# POWER.net
KiCad netlist of a schematic drawn in Altium Designer
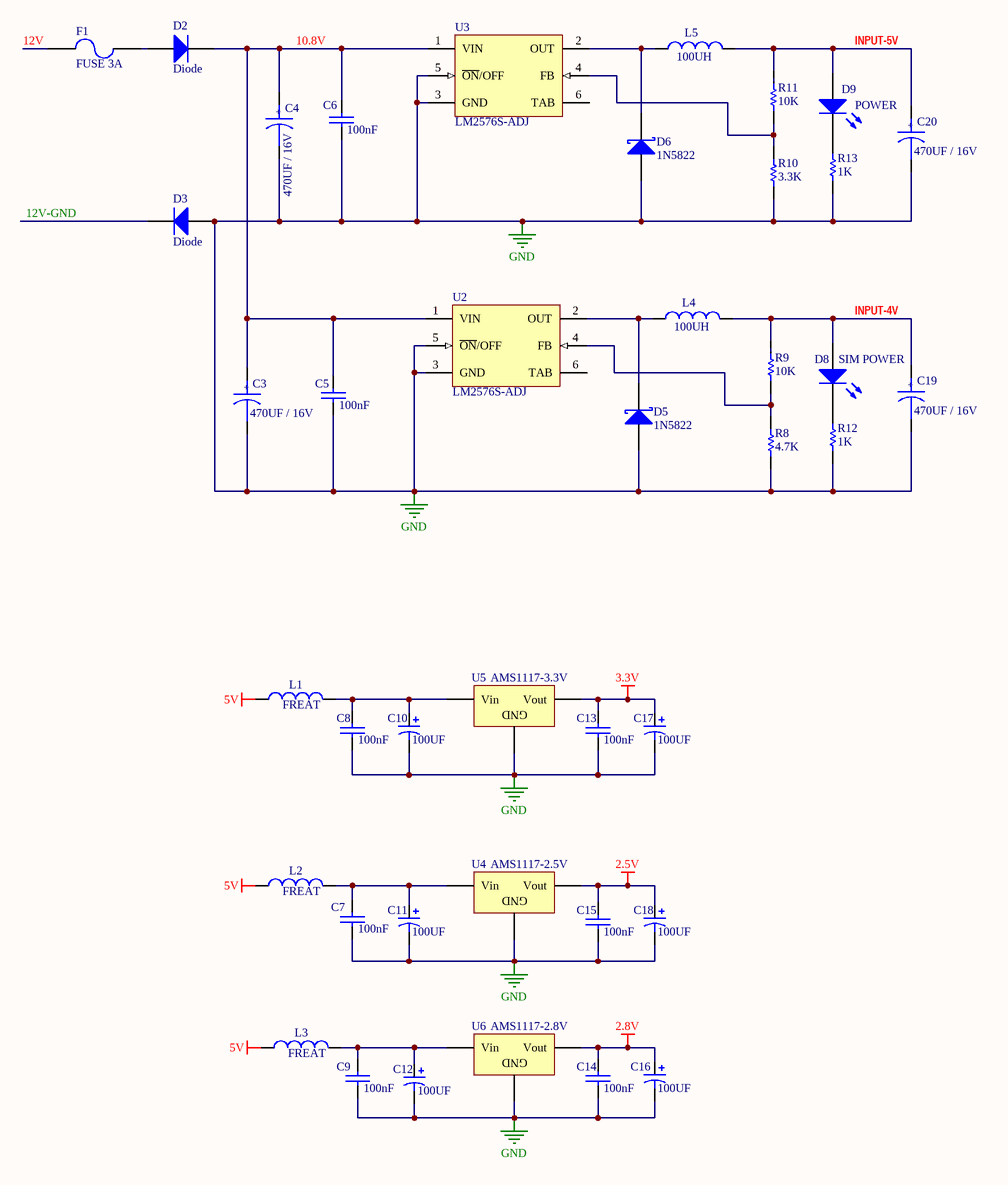
[diagram p0: POWER.SchDoc]

(export (version "E")
  (design (tool "Eeschema 10.0.6"))
  (components
    (comp (ref "C3")
      (value "470UF / 16V")
      (footprint "470UF-SMD")
      (description "Capacitor")
      (libsource (lib "*") (part "CAPACITOR POL"))
    )
    (comp (ref "C4")
      (value "470UF / 16V")
      (footprint "470UF-SMD")
      (description "Capacitor")
      (libsource (lib "*") (part "CAPACITOR POL"))
    )
    (comp (ref "C5") (value "100nF") (footprint "0805C") (libsource (lib "*") (part "CAP")))
    (comp (ref "C6") (value "100nF") (footprint "0805C") (libsource (lib "*") (part "CAP")))
    (comp (ref "C7") (value "100nF") (footprint "0805C") (libsource (lib "*") (part "CAP")))
    (comp (ref "C8") (value "100nF") (footprint "0805C") (libsource (lib "*") (part "CAP")))
    (comp (ref "C9") (value "100nF") (footprint "0805C") (libsource (lib "*") (part "CAP")))
    (comp (ref "C10")
      (value "100UF")
      (footprint "100UF-SMD")
      (description "Polarized Capacitor (Radial)")
      (fields (field (name "Comment") "100uF / 16V SMD") (field (name "PUBLISHER") "Altium Limited"))
      (libsource (lib "Miscellaneous Devices") (part "Cap Pol1"))
    )
    (comp (ref "C11")
      (value "100UF")
      (footprint "100uf-smd")
      (description "Polarized Capacitor (Radial)")
      (fields (field (name "Comment") "100uF / 16V SMD") (field (name "PUBLISHER") "Altium Limited"))
      (libsource (lib "Miscellaneous Devices") (part "Cap Pol1"))
    )
    (comp (ref "C12")
      (value "100UF")
      (footprint "100uf-smd")
      (description "Polarized Capacitor (Radial)")
      (fields (field (name "Comment") "100uF / 16V SMD") (field (name "PUBLISHER") "Altium Limited"))
      (libsource (lib "Miscellaneous Devices") (part "Cap Pol1"))
    )
    (comp (ref "C13") (value "100nF") (footprint "0805C") (libsource (lib "*") (part "CAP")))
    (comp (ref "C14") (value "100nF") (footprint "0805C") (libsource (lib "*") (part "CAP")))
    (comp (ref "C15") (value "100nF") (footprint "0805C") (libsource (lib "*") (part "CAP")))
    (comp (ref "C16")
      (value "100UF")
      (footprint "100uf-smd")
      (description "Polarized Capacitor (Radial)")
      (fields (field (name "Comment") "100uF / 16V SMD") (field (name "PUBLISHER") "Altium Limited"))
      (libsource (lib "Miscellaneous Devices") (part "Cap Pol1"))
    )
    (comp (ref "C17")
      (value "100UF")
      (footprint "100uf-smd")
      (description "Polarized Capacitor (Radial)")
      (fields (field (name "Comment") "100uF / 16V SMD") (field (name "PUBLISHER") "Altium Limited"))
      (libsource (lib "Miscellaneous Devices") (part "Cap Pol1"))
    )
    (comp (ref "C18")
      (value "100UF")
      (footprint "100uf-smd")
      (description "Polarized Capacitor (Radial)")
      (fields (field (name "Comment") "100uF / 16V SMD") (field (name "PUBLISHER") "Altium Limited"))
      (libsource (lib "Miscellaneous Devices") (part "Cap Pol1"))
    )
    (comp (ref "C19")
      (value "470UF / 16V")
      (footprint "470UF-SMD")
      (description "Capacitor")
      (libsource (lib "*") (part "CAPACITOR POL"))
    )
    (comp (ref "C20")
      (value "470UF / 16V")
      (footprint "470UF-SMD")
      (description "Capacitor")
      (libsource (lib "*") (part "CAPACITOR POL"))
    )
    (comp (ref "D2")
      (value "Diode")
      (footprint "Diode")
      (description "Default Diode")
      (fields (field (name "PUBLISHER") "Altium Limited"))
      (libsource (lib "Miscellaneous Devices") (part "Diode"))
    )
    (comp (ref "D3")
      (value "Diode")
      (footprint "Diode")
      (description "Default Diode")
      (fields (field (name "PUBLISHER") "Altium Limited"))
      (libsource (lib "Miscellaneous Devices") (part "Diode"))
    )
    (comp (ref "D5")
      (value "1N5822")
      (footprint "SMB")
      (description "Schottky Diode")
      (fields (field (name "PUBLISHER") "Altium Limited"))
      (libsource (lib "Miscellaneous Devices") (part "D Schottky"))
    )
    (comp (ref "D6")
      (value "1N5822")
      (footprint "SMB")
      (description "Schottky Diode")
      (fields (field (name "PUBLISHER") "Altium Limited"))
      (libsource (lib "Miscellaneous Devices") (part "D Schottky"))
    )
    (comp (ref "D8")
      (value "LED")
      (footprint "0805D")
      (description "Typical BLUE SiC LED")
      (fields (field (name "PUBLISHER") "SIM POWER"))
      (libsource (lib "Miscellaneous Devices") (part "LED3"))
    )
    (comp (ref "D9")
      (value "LED")
      (footprint "0805D")
      (description "Typical BLUE SiC LED")
      (fields (field (name "POWER") "POWER"))
      (libsource (lib "Miscellaneous Devices") (part "LED3"))
    )
    (comp (ref "F1")
      (value "FUSE 3A")
      (footprint "FUSE")
      (description "Fuse")
      (libsource (lib "*") (part "FUSE2"))
    )
    (comp (ref "L1")
      (value "FREAT")
      (footprint "1206")
      (description "Inductor")
      (fields (field (name "PUBLISHER") "Altium Limited"))
      (libsource (lib "Miscellaneous Devices") (part "Inductor"))
    )
    (comp (ref "L2")
      (value "FREAT")
      (footprint "1206")
      (description "Inductor")
      (fields (field (name "PUBLISHER") "Altium Limited"))
      (libsource (lib "Miscellaneous Devices") (part "Inductor"))
    )
    (comp (ref "L3")
      (value "FREAT")
      (footprint "1206")
      (description "Inductor")
      (fields (field (name "PUBLISHER") "Altium Limited"))
      (libsource (lib "Miscellaneous Devices") (part "Inductor"))
    )
    (comp (ref "L4")
      (value "100UH")
      (footprint "100UH 1")
      (description "Inductor")
      (fields (field (name "PUBLISHER") "Altium Limited"))
      (libsource (lib "Miscellaneous Devices") (part "Inductor"))
    )
    (comp (ref "L5")
      (value "100UH")
      (footprint "100UH 1")
      (description "Inductor")
      (fields (field (name "PUBLISHER") "Altium Limited"))
      (libsource (lib "Miscellaneous Devices") (part "Inductor"))
    )
    (comp (ref "R8")
      (value "4.7K")
      (footprint "0805")
      (description "Semiconductor Resistor")
      (fields (field (name "PUBLISHER") "Altium Limited"))
      (libsource (lib "Miscellaneous Devices") (part "Res Semi"))
    )
    (comp (ref "R9")
      (value "10K")
      (footprint "0805")
      (description "Semiconductor Resistor")
      (fields (field (name "PUBLISHER") "Altium Limited"))
      (libsource (lib "Miscellaneous Devices") (part "Res Semi"))
    )
    (comp (ref "R10")
      (value "3.3K")
      (footprint "0805")
      (description "Semiconductor Resistor")
      (fields (field (name "PUBLISHER") "Altium Limited"))
      (libsource (lib "Miscellaneous Devices") (part "Res Semi"))
    )
    (comp (ref "R11")
      (value "10K")
      (footprint "0805")
      (description "Semiconductor Resistor")
      (fields (field (name "PUBLISHER") "Altium Limited"))
      (libsource (lib "Miscellaneous Devices") (part "Res Semi"))
    )
    (comp (ref "R12")
      (value "1K")
      (footprint "0805")
      (description "Resistor")
      (fields (field (name "PUBLISHER") "Altium Limited"))
      (libsource (lib "*") (part "Res1"))
    )
    (comp (ref "R13")
      (value "1K")
      (footprint "0805")
      (description "Resistor")
      (fields (field (name "PUBLISHER") "Altium Limited"))
      (libsource (lib "*") (part "Res1"))
    )
    (comp (ref "U2")
      (value "LM2576S-ADJ")
      (footprint "TS5B_N")
      (description "SIMPLE SWITCHER® 3A Step-Down Voltage Regulator, 5-pin TO-263")
      (fields
        (field (name "MANUFACTURER") "National Semiconductor")
        (field (name "PUBLISHER") "Altium Limited")
      )
      (libsource (lib "NSC Switcher") (part "LM2576S-ADJ"))
    )
    (comp (ref "U3")
      (value "LM2576S-ADJ")
      (footprint "TS5B_N")
      (description "SIMPLE SWITCHER® 3A Step-Down Voltage Regulator, 5-pin TO-263")
      (fields
        (field (name "MANUFACTURER") "National Semiconductor")
        (field (name "PUBLISHER") "Altium Limited")
      )
      (libsource (lib "NSC Switcher") (part "LM2576S-ADJ"))
    )
    (comp (ref "U4")
      (value "AMS1117-2.5V")
      (footprint "sot223")
      (description "Voltage Regulator")
      (fields (field (name "PUBLISHER") "Altium Limited"))
      (libsource (lib "SmartHome V2") (part "Volt Reg"))
    )
    (comp (ref "U5")
      (value "AMS1117-3.3V")
      (footprint "sot223")
      (description "Voltage Regulator")
      (fields (field (name "PUBLISHER") "Altium Limited"))
      (libsource (lib "SmartHome V2") (part "Volt Reg"))
    )
    (comp (ref "U6")
      (value "AMS1117-2.8V")
      (footprint "sot223")
      (description "Voltage Regulator")
      (fields (field (name "PUBLISHER") "Altium Limited"))
      (libsource (lib "SmartHome V2") (part "Volt Reg"))
    )
  )
  (nets
    (net (code "1") (name "/10.8V") (class "Default")
      (node (ref "C3") (pin "1") (pinfunction "1_1") (pintype "passive"))
      (node (ref "C4") (pin "1") (pinfunction "1_1") (pintype "passive"))
      (node (ref "C5") (pin "1") (pintype "passive"))
      (node (ref "C6") (pin "1") (pintype "passive"))
      (node (ref "D2") (pin "2") (pinfunction "K_2") (pintype "passive"))
      (node (ref "U2") (pin "1") (pinfunction "VIN_1") (pintype "power_in"))
      (node (ref "U3") (pin "1") (pinfunction "VIN_1") (pintype "power_in"))
    )
    (net (code "2") (name "/12V") (class "Default")
      (node (ref "F1") (pin "1") (pinfunction "1_1") (pintype "passive"))
    )
    (net (code "3") (name "/12V-GND") (class "Default")
      (node (ref "D3") (pin "2") (pinfunction "K_2") (pintype "passive"))
    )
    (net (code "4") (name "/INPUT-4V") (class "Default")
      (node (ref "C19") (pin "1") (pinfunction "1_1") (pintype "passive"))
      (node (ref "D8") (pin "1") (pinfunction "A_1") (pintype "passive"))
      (node (ref "L4") (pin "2") (pinfunction "2_2") (pintype "passive"))
      (node (ref "R9") (pin "2") (pinfunction "2_2") (pintype "passive"))
    )
    (net (code "5") (name "/INPUT-5V") (class "Default")
      (node (ref "C20") (pin "1") (pinfunction "1_1") (pintype "passive"))
      (node (ref "D9") (pin "1") (pinfunction "A_1") (pintype "passive"))
      (node (ref "L5") (pin "2") (pinfunction "2_2") (pintype "passive"))
      (node (ref "R11") (pin "2") (pinfunction "2_2") (pintype "passive"))
    )
    (net (code "6") (name "2.5V") (class "Default")
      (node (ref "C15") (pin "1") (pintype "passive"))
      (node (ref "C18") (pin "1") (pinfunction "1_1") (pintype "passive"))
      (node (ref "U4") (pin "2") (pinfunction "Vout_2") (pintype "passive"))
    )
    (net (code "7") (name "2.8V") (class "Default")
      (node (ref "C14") (pin "1") (pintype "passive"))
      (node (ref "C16") (pin "1") (pinfunction "1_1") (pintype "passive"))
      (node (ref "U6") (pin "2") (pinfunction "Vout_2") (pintype "passive"))
    )
    (net (code "8") (name "3.3V") (class "Default")
      (node (ref "C13") (pin "1") (pintype "passive"))
      (node (ref "C17") (pin "1") (pinfunction "1_1") (pintype "passive"))
      (node (ref "U5") (pin "2") (pinfunction "Vout_2") (pintype "passive"))
    )
    (net (code "9") (name "5V") (class "Default")
      (node (ref "L1") (pin "1") (pinfunction "1_1") (pintype "passive"))
      (node (ref "L2") (pin "1") (pinfunction "1_1") (pintype "passive"))
      (node (ref "L3") (pin "1") (pinfunction "1_1") (pintype "passive"))
    )
    (net (code "10") (name "GND") (class "Default")
      (node (ref "C10") (pin "2") (pinfunction "2_2") (pintype "passive"))
      (node (ref "C11") (pin "2") (pinfunction "2_2") (pintype "passive"))
      (node (ref "C12") (pin "2") (pinfunction "2_2") (pintype "passive"))
      (node (ref "C13") (pin "2") (pintype "passive"))
      (node (ref "C14") (pin "2") (pintype "passive"))
      (node (ref "C15") (pin "2") (pintype "passive"))
      (node (ref "C16") (pin "2") (pinfunction "2_2") (pintype "passive"))
      (node (ref "C17") (pin "2") (pinfunction "2_2") (pintype "passive"))
      (node (ref "C18") (pin "2") (pinfunction "2_2") (pintype "passive"))
      (node (ref "C19") (pin "2") (pinfunction "2_2") (pintype "passive"))
      (node (ref "C20") (pin "2") (pinfunction "2_2") (pintype "passive"))
      (node (ref "C3") (pin "2") (pinfunction "2_2") (pintype "passive"))
      (node (ref "C4") (pin "2") (pinfunction "2_2") (pintype "passive"))
      (node (ref "C5") (pin "2") (pintype "passive"))
      (node (ref "C6") (pin "2") (pintype "passive"))
      (node (ref "C7") (pin "2") (pintype "passive"))
      (node (ref "C8") (pin "2") (pintype "passive"))
      (node (ref "C9") (pin "2") (pintype "passive"))
      (node (ref "D3") (pin "1") (pinfunction "A_1") (pintype "passive"))
      (node (ref "D5") (pin "1") (pinfunction "A_1") (pintype "passive"))
      (node (ref "D6") (pin "1") (pinfunction "A_1") (pintype "passive"))
      (node (ref "R10") (pin "1") (pinfunction "1_1") (pintype "passive"))
      (node (ref "R12") (pin "2") (pinfunction "2_2") (pintype "passive"))
      (node (ref "R13") (pin "2") (pinfunction "2_2") (pintype "passive"))
      (node (ref "R8") (pin "1") (pinfunction "1_1") (pintype "passive"))
      (node (ref "U2") (pin "3") (pinfunction "GND_3") (pintype "power_in"))
      (node (ref "U2") (pin "5") (pinfunction "~{ON}/OFF_5") (pintype "input"))
      (node (ref "U3") (pin "3") (pinfunction "GND_3") (pintype "power_in"))
      (node (ref "U3") (pin "5") (pinfunction "~{ON}/OFF_5") (pintype "input"))
      (node (ref "U4") (pin "1") (pinfunction "GND_1") (pintype "passive"))
      (node (ref "U5") (pin "1") (pinfunction "GND_1") (pintype "passive"))
      (node (ref "U6") (pin "1") (pinfunction "GND_1") (pintype "passive"))
    )
    (net (code "11") (name "Net-(D2-A)") (class "Default")
      (node (ref "D2") (pin "1") (pinfunction "A_1") (pintype "passive"))
      (node (ref "F1") (pin "2") (pinfunction "2_2") (pintype "passive"))
    )
    (net (code "12") (name "Net-(D5-K)") (class "Default")
      (node (ref "D5") (pin "2") (pinfunction "K_2") (pintype "passive"))
      (node (ref "L4") (pin "1") (pinfunction "1_1") (pintype "passive"))
      (node (ref "U2") (pin "2") (pinfunction "OUT_2") (pintype "power_in"))
    )
    (net (code "13") (name "Net-(D6-K)") (class "Default")
      (node (ref "D6") (pin "2") (pinfunction "K_2") (pintype "passive"))
      (node (ref "L5") (pin "1") (pinfunction "1_1") (pintype "passive"))
      (node (ref "U3") (pin "2") (pinfunction "OUT_2") (pintype "power_in"))
    )
    (net (code "14") (name "Net-(D8-K)") (class "Default")
      (node (ref "D8") (pin "2") (pinfunction "K_2") (pintype "passive"))
      (node (ref "R12") (pin "1") (pinfunction "1_1") (pintype "passive"))
    )
    (net (code "15") (name "Net-(D9-K)") (class "Default")
      (node (ref "D9") (pin "2") (pinfunction "K_2") (pintype "passive"))
      (node (ref "R13") (pin "1") (pinfunction "1_1") (pintype "passive"))
    )
    (net (code "16") (name "Net-(U2-FB)") (class "Default")
      (node (ref "R8") (pin "2") (pinfunction "2_2") (pintype "passive"))
      (node (ref "R9") (pin "1") (pinfunction "1_1") (pintype "passive"))
      (node (ref "U2") (pin "4") (pinfunction "FB_4") (pintype "input"))
    )
    (net (code "17") (name "Net-(U3-FB)") (class "Default")
      (node (ref "R10") (pin "2") (pinfunction "2_2") (pintype "passive"))
      (node (ref "R11") (pin "1") (pinfunction "1_1") (pintype "passive"))
      (node (ref "U3") (pin "4") (pinfunction "FB_4") (pintype "input"))
    )
    (net (code "18") (name "Net-(U4-Vin)") (class "Default")
      (node (ref "C11") (pin "1") (pinfunction "1_1") (pintype "passive"))
      (node (ref "C7") (pin "1") (pintype "passive"))
      (node (ref "L2") (pin "2") (pinfunction "2_2") (pintype "passive"))
      (node (ref "U4") (pin "3") (pinfunction "Vin_3") (pintype "passive"))
    )
    (net (code "19") (name "Net-(U5-Vin)") (class "Default")
      (node (ref "C10") (pin "1") (pinfunction "1_1") (pintype "passive"))
      (node (ref "C8") (pin "1") (pintype "passive"))
      (node (ref "L1") (pin "2") (pinfunction "2_2") (pintype "passive"))
      (node (ref "U5") (pin "3") (pinfunction "Vin_3") (pintype "passive"))
    )
    (net (code "20") (name "Net-(U6-Vin)") (class "Default")
      (node (ref "C12") (pin "1") (pinfunction "1_1") (pintype "passive"))
      (node (ref "C9") (pin "1") (pintype "passive"))
      (node (ref "L3") (pin "2") (pinfunction "2_2") (pintype "passive"))
      (node (ref "U6") (pin "3") (pinfunction "Vin_3") (pintype "passive"))
    )
    (net (code "21") (name "unconnected-(U2-TAB-Pad6)") (class "Default")
      (node (ref "U2") (pin "6") (pinfunction "TAB_6") (pintype "power_in"))
    )
    (net (code "22") (name "unconnected-(U3-TAB-Pad6)") (class "Default")
      (node (ref "U3") (pin "6") (pinfunction "TAB_6") (pintype "power_in"))
    )
  )
)
